# GBTx_MGT.net
KiCad netlist of a schematic drawn in Altium Designer
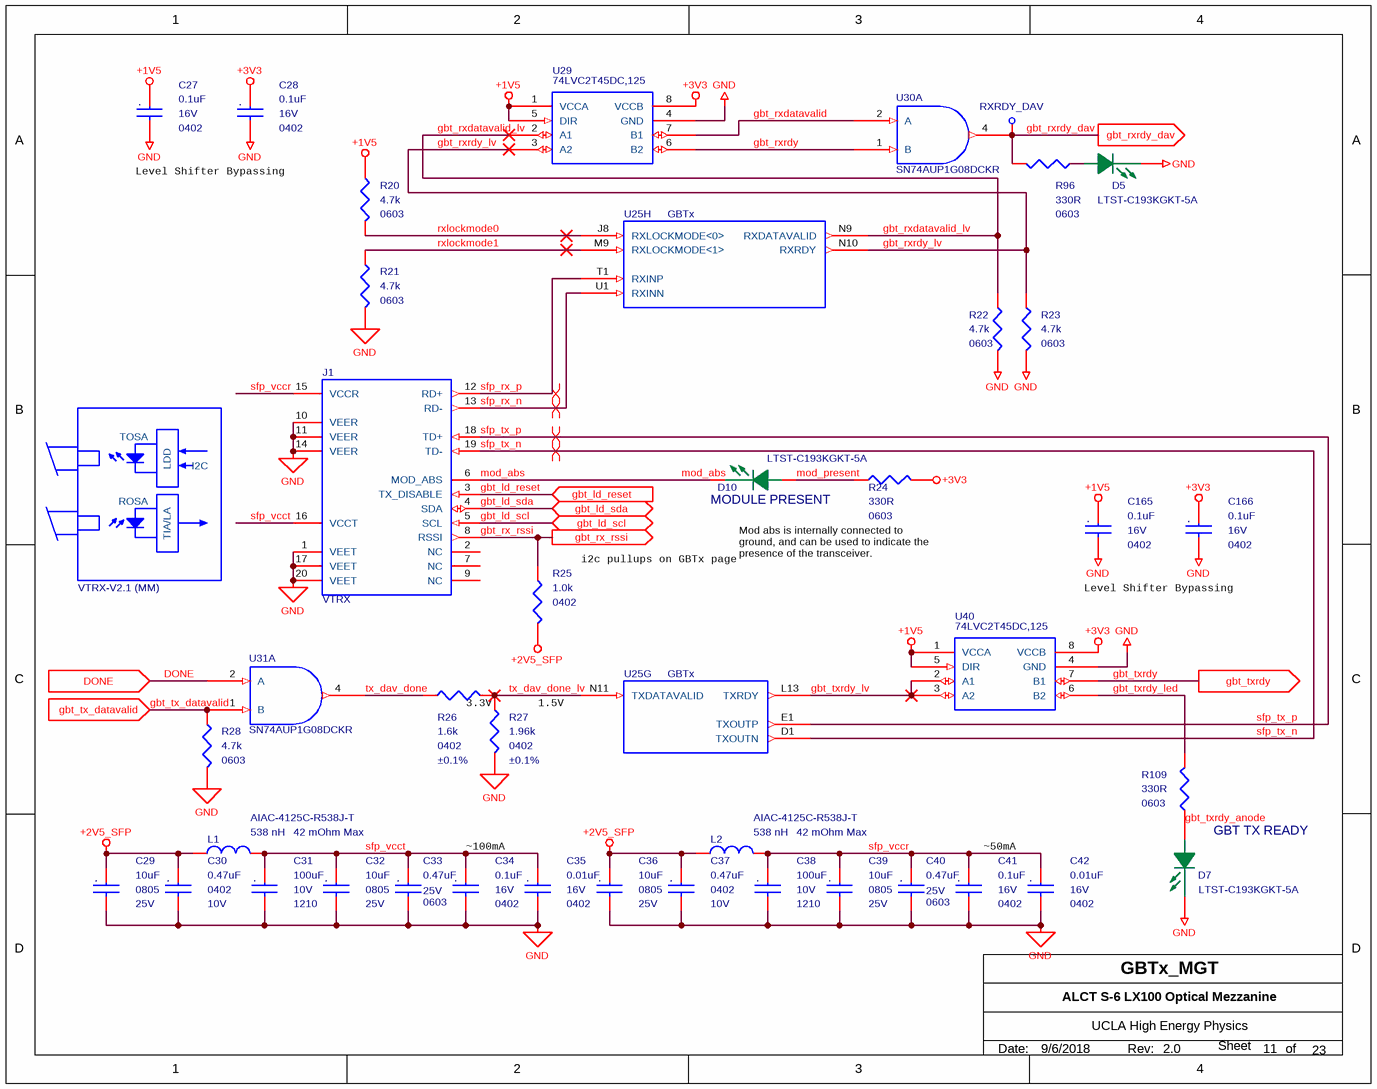
[diagram p0: GBTx_MGT.SchDoc]

(export (version "E")
  (design (tool "Eeschema 10.0.6"))
  (components
    (comp (ref "C27")
      (value "0.1uF")
      (footprint "MC_S6/SM/C_0402_IPC")
      (description "CAP CER 0.1UF 16V X7R 0402")
      (fields
        (field (name "MANUFACTURER") "KEMET")
        (field (name "MANUFACTURER PART NUMBER") "C0402C104K4RACTU")
        (field (name "PACKAGE") "0402")
        (field (name "VOLTAGE - RATED") "16V")
      )
      (libsource (lib "ALCT_MEZ_SPARTAN6_Library") (part "C0402C104K4RACTU"))
    )
    (comp (ref "C28")
      (value "0.1uF")
      (footprint "MC_S6/SM/C_0402_IPC")
      (description "CAP CER 0.1UF 16V X7R 0402")
      (fields
        (field (name "MANUFACTURER") "KEMET")
        (field (name "MANUFACTURER PART NUMBER") "C0402C104K4RACTU")
        (field (name "PACKAGE") "0402")
        (field (name "VOLTAGE - RATED") "16V")
      )
      (libsource (lib "ALCT_MEZ_SPARTAN6_Library") (part "C0402C104K4RACTU"))
    )
    (comp (ref "C29")
      (value "10uF")
      (footprint "MC_S6/SM/C_0805_IPC")
      (description "CAP CER 10UF 25V X5R 0805")
      (fields
        (field (name "MANUFACTURER") "Murata Electronics North America")
        (field (name "MANUFACTURER PART NUMBER") "GRM21BR61E106KA73L")
        (field (name "VOLTAGE - RATED") "25V")
        (field (name "PACKAGE") "0805")
      )
      (libsource (lib "ALCT_MEZ_SPARTAN6_Library") (part "GRM21BR61E106KA73L"))
    )
    (comp (ref "C30")
      (value "0.47uF")
      (footprint "MC_S6/SM/C_0402_IPC")
      (description "CAP CER 0.47UF 10V X5R 0402")
      (fields
        (field (name "MANUFACTURER") "Murata Electronics North America")
        (field (name "MANUFACTURER PART NUMBER") "GRM155R61A474KE15D")
        (field (name "VOLTAGE - RATED") "10V")
        (field (name "PACKAGE") "0402")
      )
      (libsource (lib "ALCT_MEZ_SPARTAN6_Library") (part "GRM155R61A474KE15D"))
    )
    (comp (ref "C31")
      (value "100uF")
      (footprint "MC_S6/SM/C_1210_IPC")
      (description "CAP CER 100UF 10V X5R 1210")
      (fields
        (field (name "MANUFACTURER") "Taiyo Yuden")
        (field (name "MANUFACTURER PART NUMBER") "LMK325BJ107MM-T")
        (field (name "VOLTAGE - RATED") "10V")
        (field (name "PACKAGE") "1210")
      )
      (libsource (lib "ALCT_MEZ_SPARTAN6_Library") (part "LMK325BJ107MM-T"))
    )
    (comp (ref "C32")
      (value "10uF")
      (footprint "MC_S6/SM/C_0805_IPC")
      (description "CAP CER 10UF 25V X5R 0805")
      (fields
        (field (name "MANUFACTURER") "Murata Electronics North America")
        (field (name "MANUFACTURER PART NUMBER") "GRM21BR61E106KA73L")
        (field (name "VOLTAGE - RATED") "25V")
        (field (name "PACKAGE") "0805")
      )
      (libsource (lib "ALCT_MEZ_SPARTAN6_Library") (part "GRM21BR61E106KA73L"))
    )
    (comp (ref "C33")
      (value "0.47uF")
      (footprint "MC_S6/SM/C_0603_IPC")
      (description "CAP CER 0.47UF 25V X7R 0603")
      (fields
        (field (name "MANUFACTURER") "Murata")
        (field (name "MANUFACTURER PART NUMBER") "GRM188R71E474KA12D")
        (field (name "VOLTAGE - RATED") "25V")
        (field (name "PACKAGE") "0603")
      )
      (libsource (lib "ALCT_MEZ_SPARTAN6_Library") (part "GRM188R71E474KA12D"))
    )
    (comp (ref "C34")
      (value "0.1uF")
      (footprint "MC_S6/SM/C_0402_IPC")
      (description "CAP CER 0.1UF 16V X7R 0402")
      (fields
        (field (name "MANUFACTURER") "KEMET")
        (field (name "MANUFACTURER PART NUMBER") "C0402C104K4RACTU")
        (field (name "PACKAGE") "0402")
        (field (name "VOLTAGE - RATED") "16V")
      )
      (libsource (lib "ALCT_MEZ_SPARTAN6_Library") (part "C0402C104K4RACTU"))
    )
    (comp (ref "C35")
      (value "0.01uF")
      (footprint "MC_S6/SM/C_0402_IPC")
      (description "CAP CER 10nF 16V X7R 0402")
      (fields
        (field (name "MANUFACTURER") "KEMET")
        (field (name "MANUFACTURER PART NUMBER") "C0402C103K4RACTU")
        (field (name "VOLTAGE - RATED") "16V")
        (field (name "PACKAGE") "0402")
      )
      (libsource (lib "ALCT_MEZ_SPARTAN6_Library") (part "C0402C103K4RACTU"))
    )
    (comp (ref "C36")
      (value "10uF")
      (footprint "MC_S6/SM/C_0805_IPC")
      (description "CAP CER 10UF 25V X5R 0805")
      (fields
        (field (name "MANUFACTURER") "Murata Electronics North America")
        (field (name "MANUFACTURER PART NUMBER") "GRM21BR61E106KA73L")
        (field (name "VOLTAGE - RATED") "25V")
        (field (name "PACKAGE") "0805")
      )
      (libsource (lib "ALCT_MEZ_SPARTAN6_Library") (part "GRM21BR61E106KA73L"))
    )
    (comp (ref "C37")
      (value "0.47uF")
      (footprint "MC_S6/SM/C_0402_IPC")
      (description "CAP CER 0.47UF 10V X5R 0402")
      (fields
        (field (name "MANUFACTURER") "Murata Electronics North America")
        (field (name "MANUFACTURER PART NUMBER") "GRM155R61A474KE15D")
        (field (name "VOLTAGE - RATED") "10V")
        (field (name "PACKAGE") "0402")
      )
      (libsource (lib "ALCT_MEZ_SPARTAN6_Library") (part "GRM155R61A474KE15D"))
    )
    (comp (ref "C38")
      (value "100uF")
      (footprint "MC_S6/SM/C_1210_IPC")
      (description "CAP CER 100UF 10V X5R 1210")
      (fields
        (field (name "MANUFACTURER") "Taiyo Yuden")
        (field (name "MANUFACTURER PART NUMBER") "LMK325BJ107MM-T")
        (field (name "VOLTAGE - RATED") "10V")
        (field (name "PACKAGE") "1210")
      )
      (libsource (lib "ALCT_MEZ_SPARTAN6_Library") (part "LMK325BJ107MM-T"))
    )
    (comp (ref "C39")
      (value "10uF")
      (footprint "MC_S6/SM/C_0805_IPC")
      (description "CAP CER 10UF 25V X5R 0805")
      (fields
        (field (name "MANUFACTURER") "Murata Electronics North America")
        (field (name "MANUFACTURER PART NUMBER") "GRM21BR61E106KA73L")
        (field (name "VOLTAGE - RATED") "25V")
        (field (name "PACKAGE") "0805")
      )
      (libsource (lib "ALCT_MEZ_SPARTAN6_Library") (part "GRM21BR61E106KA73L"))
    )
    (comp (ref "C40")
      (value "0.47uF")
      (footprint "MC_S6/SM/C_0603_IPC")
      (description "CAP CER 0.47UF 25V X7R 0603")
      (fields
        (field (name "MANUFACTURER") "Murata")
        (field (name "MANUFACTURER PART NUMBER") "GRM188R71E474KA12D")
        (field (name "VOLTAGE - RATED") "25V")
        (field (name "PACKAGE") "0603")
      )
      (libsource (lib "ALCT_MEZ_SPARTAN6_Library") (part "GRM188R71E474KA12D"))
    )
    (comp (ref "C41")
      (value "0.1uF")
      (footprint "MC_S6/SM/C_0402_IPC")
      (description "CAP CER 0.1UF 16V X7R 0402")
      (fields
        (field (name "MANUFACTURER") "KEMET")
        (field (name "MANUFACTURER PART NUMBER") "C0402C104K4RACTU")
        (field (name "PACKAGE") "0402")
        (field (name "VOLTAGE - RATED") "16V")
      )
      (libsource (lib "ALCT_MEZ_SPARTAN6_Library") (part "C0402C104K4RACTU"))
    )
    (comp (ref "C42")
      (value "0.01uF")
      (footprint "MC_S6/SM/C_0402_IPC")
      (description "CAP CER 10nF 16V X7R 0402")
      (fields
        (field (name "MANUFACTURER") "KEMET")
        (field (name "MANUFACTURER PART NUMBER") "C0402C103K4RACTU")
        (field (name "VOLTAGE - RATED") "16V")
        (field (name "PACKAGE") "0402")
      )
      (libsource (lib "ALCT_MEZ_SPARTAN6_Library") (part "C0402C103K4RACTU"))
    )
    (comp (ref "C165")
      (value "0.1uF")
      (footprint "MC_S6/SM/C_0402_IPC")
      (description "CAP CER 0.1UF 16V X7R 0402")
      (fields
        (field (name "MANUFACTURER") "KEMET")
        (field (name "MANUFACTURER PART NUMBER") "C0402C104K4RACTU")
        (field (name "PACKAGE") "0402")
        (field (name "VOLTAGE - RATED") "16V")
      )
      (libsource (lib "ALCT_MEZ_SPARTAN6_Library") (part "C0402C104K4RACTU"))
    )
    (comp (ref "C166")
      (value "0.1uF")
      (footprint "MC_S6/SM/C_0402_IPC")
      (description "CAP CER 0.1UF 16V X7R 0402")
      (fields
        (field (name "MANUFACTURER") "KEMET")
        (field (name "MANUFACTURER PART NUMBER") "C0402C104K4RACTU")
        (field (name "PACKAGE") "0402")
        (field (name "VOLTAGE - RATED") "16V")
      )
      (libsource (lib "ALCT_MEZ_SPARTAN6_Library") (part "C0402C104K4RACTU"))
    )
    (comp (ref "D5")
      (value "LTST-C193KGKT-5A")
      (footprint "MC_S6/SM/LED_0603")
      (description "LED GREEN CLEAR 0603 SMD")
      (fields (field (name "MANUFACTURER") "Lite-On Inc."))
      (libsource (lib "ALCT_MEZ_SPARTAN6_Library") (part "LTST-C193KGKT-5A"))
    )
    (comp (ref "D7")
      (value "LTST-C193KGKT-5A")
      (footprint "MC_S6/SM/LED_0603")
      (description "LED GREEN CLEAR 0603 SMD")
      (fields (field (name "MANUFACTURER") "Lite-On Inc."))
      (libsource (lib "ALCT_MEZ_SPARTAN6_Library") (part "LTST-C193KGKT-5A"))
    )
    (comp (ref "D10")
      (value "LTST-C193KGKT-5A")
      (footprint "MC_S6/SM/LED_0603")
      (description "LED GREEN CLEAR 0603 SMD")
      (fields (field (name "MANUFACTURER") "Lite-On Inc."))
      (libsource (lib "ALCT_MEZ_SPARTAN6_Library") (part "LTST-C193KGKT-5A"))
    )
    (comp (ref "J1")
      (value "VTRX")
      (footprint "MC_S6/SM/TE-1888247-1")
      (description "CONN FP+ CAGE 30AU SMD")
      (fields
        (field (name "MANUFACTURER") "TE Connectivity AMP Connectors")
        (field (name "MANUFACTURER PART NUMBER") "1888247-1")
      )
      (libsource (lib "ALCT_MEZ_SPARTAN6_Library") (part "VTRX"))
    )
    (comp (ref "L1")
      (value "538 nH")
      (footprint "AIAC-4125C-R538J")
      (description "IND 538NH 2A 42 MOHM SMD")
      (fields
        (field (name "MANUFACTURER") "Abracon LLC")
        (field (name "TOLERANCE") "±5%")
        (field (name "MANUFACTURER PART NUMBER") "AIAC-4125C-R538J-T")
        (field (name "DC RESISTANCE (DCR)") "42 mOhm Max")
      )
      (libsource (lib "ALCT_MEZ_SPARTAN6_Library") (part "AIAC-4125C-R538J"))
    )
    (comp (ref "L2")
      (value "538 nH")
      (footprint "AIAC-4125C-R538J")
      (description "IND 538NH 2A 42 MOHM SMD")
      (fields
        (field (name "MANUFACTURER") "Abracon LLC")
        (field (name "TOLERANCE") "±5%")
        (field (name "MANUFACTURER PART NUMBER") "AIAC-4125C-R538J-T")
        (field (name "DC RESISTANCE (DCR)") "42 mOhm Max")
      )
      (libsource (lib "ALCT_MEZ_SPARTAN6_Library") (part "AIAC-4125C-R538J"))
    )
    (comp (ref "PCBM1")
      (value "VTRX-V2.1 (MM)")
      (footprint "PCBM_CERN_VTRX V2.1 (MM)")
      (description "CERN VTRX V2.1 Multi-Mode (MM)")
      (fields
        (field (name "PART NUMBER") "PCBM_CERN_VTRX V2.1 (MM)_a")
        (field (name "MANUFACTURER") "CERN")
        (field (name "MANUFACTURER PART NUMBER") "VTRX-V2.1 (MM)")
        (field (name "AUTHOR") "CERN DEM JLC")
      )
      (libsource (lib "VTRX-VTTX") (part "PCBM_CERN_VTRX V2.1 (MM)_a"))
    )
    (comp (ref "R20")
      (value "4.7k")
      (footprint "MC_S6/SM/R_0603_IPC")
      (description "RES SMD 4.7K OHM 1% 1/10W 0603")
      (fields
        (field (name "TOLERANCE") "±1%")
        (field (name "MANUFACTURER") "Bourns Inc.")
        (field (name "SUPPLIER DEVICE PACKAGE") "0603")
      )
      (libsource (lib "ALCT_MEZ_SPARTAN6_Library") (part "CR0603-FX-4701ELF"))
    )
    (comp (ref "R21")
      (value "4.7k")
      (footprint "MC_S6/SM/R_0603_IPC")
      (description "RES SMD 4.7K OHM 1% 1/10W 0603")
      (fields
        (field (name "MANUFACTURER") "Bourns Inc.")
        (field (name "MANUFACTURER PART NUMBER") "CR0603-FX-4701ELF")
        (field (name "SUPPLIER DEVICE PACKAGE") "0603")
      )
      (libsource (lib "ALCT_MEZ_SPARTAN6_Library") (part "CR0603-FX-4701ELF"))
    )
    (comp (ref "R22")
      (value "4.7k")
      (footprint "MC_S6/SM/R_0603_IPC")
      (description "RES SMD 4.7K OHM 1% 1/10W 0603")
      (fields
        (field (name "MANUFACTURER") "Bourns Inc.")
        (field (name "MANUFACTURER PART NUMBER") "CR0603-FX-4701ELF")
        (field (name "SUPPLIER DEVICE PACKAGE") "0603")
      )
      (libsource (lib "ALCT_MEZ_SPARTAN6_Library") (part "CR0603-FX-4701ELF"))
    )
    (comp (ref "R23")
      (value "4.7k")
      (footprint "MC_S6/SM/R_0603_IPC")
      (description "RES SMD 4.7K OHM 1% 1/10W 0603")
      (fields
        (field (name "MANUFACTURER") "Bourns Inc.")
        (field (name "MANUFACTURER PART NUMBER") "CR0603-FX-4701ELF")
        (field (name "SUPPLIER DEVICE PACKAGE") "0603")
      )
      (libsource (lib "ALCT_MEZ_SPARTAN6_Library") (part "CR0603-FX-4701ELF"))
    )
    (comp (ref "R24")
      (value "330R")
      (footprint "MC_S6/SM/R_0603_IPC")
      (description "RES SMD 330 OHM 1% 1/10W 0603")
      (fields
        (field (name "TOLERANCE") "±1%")
        (field (name "MANUFACTURER") "Bourns Inc.")
        (field (name "SUPPLIER DEVICE PACKAGE") "0603")
      )
      (libsource (lib "ALCT_MEZ_SPARTAN6_Library") (part "CR0603-FX-3300ELF"))
    )
    (comp (ref "R25")
      (value "1.0k")
      (footprint "MC_S6/SM/R_0402_IPC")
      (description "RES SMD 1.0K OHM 0.1% 1/16W 0402")
      (fields
        (field (name "TOLERANCE") "±0.1%")
        (field (name "MANUFACTURER") "Panasonic Electronic Components")
        (field (name "PACKAGE") "0402")
      )
      (libsource (lib "ALCT_MEZ_SPARTAN6_Library") (part "ERA-2AEB102X"))
    )
    (comp (ref "R26")
      (value "1.6k")
      (footprint "MC_S6/SM/R_0402_IPC")
      (description "RES SMD 1.6K OHM 0.1% 1/16W 0402")
      (fields
        (field (name "MANUFACTURER") "Panasonic Electronic Components")
        (field (name "MANUFACTURER PART NUMBER") "ERA-2AEB162X")
        (field (name "TOLERANCE") "±0.1%")
        (field (name "PACKAGE") "0402")
      )
      (libsource (lib "ALCT_MEZ_SPARTAN6_Library") (part "ERA-2AEB162X"))
    )
    (comp (ref "R27")
      (value "1.96k")
      (footprint "MC_S6/SM/R_0402_IPC")
      (description "RES SMD 1.96K OHM 0.1% 1/16W 0402")
      (fields
        (field (name "MANUFACTURER") "Panasonic Electronic Components")
        (field (name "MANUFACTURER PART NUMBER") "ERA-2AEB1961X")
        (field (name "TOLERANCE") "±0.1%")
        (field (name "PACKAGE") "0402")
      )
      (libsource (lib "ALCT_MEZ_SPARTAN6_Library") (part "ERA-2AEB1961X"))
    )
    (comp (ref "R28")
      (value "4.7k")
      (footprint "MC_S6/SM/R_0603_IPC")
      (description "RES SMD 4.7K OHM 1% 1/10W 0603")
      (fields
        (field (name "MANUFACTURER") "Bourns Inc.")
        (field (name "MANUFACTURER PART NUMBER") "CR0603-FX-4701ELF")
        (field (name "SUPPLIER DEVICE PACKAGE") "0603")
      )
      (libsource (lib "ALCT_MEZ_SPARTAN6_Library") (part "CR0603-FX-4701ELF"))
    )
    (comp (ref "R96")
      (value "330R")
      (footprint "MC_S6/SM/R_0603_IPC")
      (description "RES SMD 330 OHM 1% 1/10W 0603")
      (fields
        (field (name "TOLERANCE") "±1%")
        (field (name "MANUFACTURER") "Bourns Inc.")
        (field (name "SUPPLIER DEVICE PACKAGE") "0603")
      )
      (libsource (lib "ALCT_MEZ_SPARTAN6_Library") (part "CR0603-FX-3300ELF"))
    )
    (comp (ref "R109")
      (value "330R")
      (footprint "MC_S6/SM/R_0603_IPC")
      (description "RES SMD 330 OHM 1% 1/10W 0603")
      (fields
        (field (name "TOLERANCE") "±1%")
        (field (name "MANUFACTURER") "Bourns Inc.")
        (field (name "SUPPLIER DEVICE PACKAGE") "0603")
      )
      (libsource (lib "ALCT_MEZ_SPARTAN6_Library") (part "CR0603-FX-3300ELF"))
    )
    (comp (ref "RXRDY_DAV")
      (value "Test Point Via")
      (footprint "MC_S6/TH/TPVIA")
      (libsource (lib "ALCT_MEZ_SPARTAN6_Library") (part "TPVIA"))
    )
    (comp (ref "U25")
      (value "GBTx")
      (footprint "BGA400 GBT")
      (libsource (lib "ALCT_MEZ_SPARTAN6_Library") (part "GBTx"))
    )
    (comp (ref "U29")
      (value "74LVC2T45DC,125")
      (footprint "VSSOP8 SOT765-1")
      (description "IC TRNSLTR BIDIRECTIONAL 8VSSOP")
      (fields (field (name "MANUFACTURER") "Nexperia USA Inc.") (field (name "BASE PART NUMBER") "74LVC2T45"))
      (libsource (lib "ALCT_MEZ_SPARTAN6_Library") (part "74LVC2T45DC,125"))
    )
    (comp (ref "U30")
      (value "SN74AUP1G08DCKR")
      (footprint "MC_S6/SM/SOT_SC70_DCK5")
      (description "IC GATE AND 1CH 2-INP 5-TSSOP")
      (fields
        (field (name "MANUFACTURER") "Texas Instruments")
        (field (name "MANUFACTURER PART NUMBER") "SN74AUP1G08DCKT")
      )
      (libsource (lib "ALCT_MEZ_SPARTAN6_Library") (part "SN74AUP1G08DCKR"))
    )
    (comp (ref "U31")
      (value "SN74AUP1G08DCKR")
      (footprint "MC_S6/SM/SOT_SC70_DCK5")
      (description "IC GATE AND 1CH 2-INP 5-TSSOP")
      (fields
        (field (name "MANUFACTURER") "Texas Instruments")
        (field (name "MANUFACTURER PART NUMBER") "SN74AUP1G08DCKT")
      )
      (libsource (lib "ALCT_MEZ_SPARTAN6_Library") (part "SN74AUP1G08DCKR"))
    )
    (comp (ref "U40")
      (value "74LVC2T45DC,125")
      (footprint "VSSOP8 SOT765-1")
      (description "IC TRNSLTR BIDIRECTIONAL 8VSSOP")
      (fields (field (name "MANUFACTURER") "Nexperia USA Inc.") (field (name "BASE PART NUMBER") "74LVC2T45"))
      (libsource (lib "ALCT_MEZ_SPARTAN6_Library") (part "74LVC2T45DC,125"))
    )
  )
  (nets
    (net (code "1") (name "+1V5") (class "Default")
      (node (ref "C165") (pin "1") (pinfunction "1_1") (pintype "passive"))
      (node (ref "C27") (pin "1") (pinfunction "1_1") (pintype "passive"))
      (node (ref "R20") (pin "1") (pinfunction "1_1") (pintype "passive"))
      (node (ref "U29") (pin "1") (pinfunction "VCCA_1") (pintype "power_in"))
      (node (ref "U29") (pin "5") (pinfunction "DIR_5") (pintype "input"))
      (node (ref "U40") (pin "1") (pinfunction "VCCA_1") (pintype "power_in"))
      (node (ref "U40") (pin "5") (pinfunction "DIR_5") (pintype "input"))
    )
    (net (code "2") (name "+2V5_SFP") (class "Default")
      (node (ref "C29") (pin "1") (pinfunction "1_1") (pintype "passive"))
      (node (ref "C30") (pin "1") (pinfunction "1_1") (pintype "passive"))
      (node (ref "C36") (pin "1") (pinfunction "1_1") (pintype "passive"))
      (node (ref "C37") (pin "1") (pinfunction "1_1") (pintype "passive"))
      (node (ref "L1") (pin "2") (pinfunction "2_2") (pintype "passive"))
      (node (ref "L2") (pin "2") (pinfunction "2_2") (pintype "passive"))
      (node (ref "R25") (pin "2") (pinfunction "2_2") (pintype "passive"))
    )
    (net (code "3") (name "+3V3") (class "Default")
      (node (ref "C166") (pin "1") (pinfunction "1_1") (pintype "passive"))
      (node (ref "C28") (pin "1") (pinfunction "1_1") (pintype "passive"))
      (node (ref "R24") (pin "2") (pinfunction "2_2") (pintype "passive"))
      (node (ref "U29") (pin "8") (pinfunction "VCCB_8") (pintype "passive"))
      (node (ref "U40") (pin "8") (pinfunction "VCCB_8") (pintype "passive"))
    )
    (net (code "4") (name "/DONE") (class "Default")
      (node (ref "U31") (pin "2") (pinfunction "A_2") (pintype "input"))
    )
    (net (code "5") (name "/gbt_ld_reset") (class "Default")
      (node (ref "J1") (pin "3") (pinfunction "TX_DISABLE_3") (pintype "input"))
    )
    (net (code "6") (name "/gbt_ld_scl") (class "Default")
      (node (ref "J1") (pin "5") (pinfunction "SCL_5") (pintype "input"))
    )
    (net (code "7") (name "/gbt_ld_sda") (class "Default")
      (node (ref "J1") (pin "4") (pinfunction "SDA_4") (pintype "bidirectional"))
    )
    (net (code "8") (name "/gbt_rx_rssi") (class "Default")
      (node (ref "J1") (pin "8") (pinfunction "RSSI_8") (pintype "output"))
      (node (ref "R25") (pin "1") (pinfunction "1_1") (pintype "passive"))
    )
    (net (code "9") (name "/gbt_rxdatavalid") (class "Default")
      (node (ref "U29") (pin "7") (pinfunction "B1_7") (pintype "bidirectional"))
      (node (ref "U30") (pin "2") (pinfunction "A_2") (pintype "input"))
    )
    (net (code "10") (name "/gbt_rxdatavalid_lv") (class "Default")
      (node (ref "R22") (pin "1") (pinfunction "1_1") (pintype "passive"))
      (node (ref "U25") (pin "N9") (pinfunction "RXDATAVALID_N9") (pintype "output"))
      (node (ref "U29") (pin "2") (pinfunction "A1_2") (pintype "bidirectional"))
    )
    (net (code "11") (name "/gbt_rxrdy") (class "Default")
      (node (ref "U29") (pin "6") (pinfunction "B2_6") (pintype "bidirectional"))
      (node (ref "U30") (pin "1") (pinfunction "B_1") (pintype "input"))
    )
    (net (code "12") (name "/gbt_rxrdy_dav") (class "Default")
      (node (ref "R96") (pin "2") (pinfunction "2_2") (pintype "passive"))
      (node (ref "RXRDY_DAV") (pin "1") (pinfunction "In_1") (pintype "passive"))
      (node (ref "U30") (pin "4") (pinfunction "Y_4") (pintype "output"))
    )
    (net (code "13") (name "/gbt_rxrdy_lv") (class "Default")
      (node (ref "R23") (pin "1") (pinfunction "1_1") (pintype "passive"))
      (node (ref "U25") (pin "N10") (pinfunction "RXRDY_N10") (pintype "output"))
      (node (ref "U29") (pin "3") (pinfunction "A2_3") (pintype "bidirectional"))
    )
    (net (code "14") (name "/gbt_tx_datavalid") (class "Default")
      (node (ref "R28") (pin "1") (pinfunction "1_1") (pintype "passive"))
      (node (ref "U31") (pin "1") (pinfunction "B_1") (pintype "input"))
    )
    (net (code "15") (name "/gbt_txrdy") (class "Default")
      (node (ref "U40") (pin "7") (pinfunction "B1_7") (pintype "bidirectional"))
    )
    (net (code "16") (name "/gbt_txrdy_anode") (class "Default")
      (node (ref "D7") (pin "A") (pinfunction "ANODE_A") (pintype "passive"))
      (node (ref "R109") (pin "1") (pinfunction "1_1") (pintype "passive"))
    )
    (net (code "17") (name "/gbt_txrdy_led") (class "Default")
      (node (ref "R109") (pin "2") (pinfunction "2_2") (pintype "passive"))
      (node (ref "U40") (pin "6") (pinfunction "B2_6") (pintype "bidirectional"))
    )
    (net (code "18") (name "/gbt_txrdy_lv") (class "Default")
      (node (ref "U25") (pin "L13") (pinfunction "TXRDY_L13") (pintype "output"))
      (node (ref "U40") (pin "2") (pinfunction "A1_2") (pintype "bidirectional"))
      (node (ref "U40") (pin "3") (pinfunction "A2_3") (pintype "bidirectional"))
    )
    (net (code "19") (name "/mod_abs") (class "Default")
      (node (ref "D10") (pin "K") (pinfunction "CATHODE_K") (pintype "passive"))
      (node (ref "J1") (pin "6") (pinfunction "MOD_ABS_6") (pintype "passive"))
    )
    (net (code "20") (name "/mod_present") (class "Default")
      (node (ref "D10") (pin "A") (pinfunction "ANODE_A") (pintype "passive"))
      (node (ref "R24") (pin "1") (pinfunction "1_1") (pintype "passive"))
    )
    (net (code "21") (name "/rxlockmode0") (class "Default")
      (node (ref "R20") (pin "2") (pinfunction "2_2") (pintype "passive"))
      (node (ref "U25") (pin "J8") (pinfunction "RXLOCKMODE<0>_J8") (pintype "input"))
    )
    (net (code "22") (name "/rxlockmode1") (class "Default")
      (node (ref "R21") (pin "1") (pinfunction "1_1") (pintype "passive"))
      (node (ref "U25") (pin "M9") (pinfunction "RXLOCKMODE<1>_M9") (pintype "input"))
    )
    (net (code "23") (name "/sfp_rx_n") (class "Default")
      (node (ref "J1") (pin "13") (pinfunction "RD-_13") (pintype "output"))
      (node (ref "U25") (pin "U1") (pinfunction "RXINN_U1") (pintype "input"))
    )
    (net (code "24") (name "/sfp_rx_p") (class "Default")
      (node (ref "J1") (pin "12") (pinfunction "RD+_12") (pintype "output"))
      (node (ref "U25") (pin "T1") (pinfunction "RXINP_T1") (pintype "input"))
    )
    (net (code "25") (name "/sfp_tx_n") (class "Default")
      (node (ref "J1") (pin "19") (pinfunction "TD-_19") (pintype "input"))
      (node (ref "U25") (pin "D1") (pinfunction "TXOUTN_D1") (pintype "output"))
    )
    (net (code "26") (name "/sfp_tx_p") (class "Default")
      (node (ref "J1") (pin "18") (pinfunction "TD+_18") (pintype "input"))
      (node (ref "U25") (pin "E1") (pinfunction "TXOUTP_E1") (pintype "output"))
    )
    (net (code "27") (name "/sfp_vccr") (class "Default")
      (node (ref "C38") (pin "1") (pinfunction "1_1") (pintype "passive"))
      (node (ref "C39") (pin "1") (pinfunction "1_1") (pintype "passive"))
      (node (ref "C40") (pin "1") (pinfunction "1_1") (pintype "passive"))
      (node (ref "C41") (pin "1") (pinfunction "1_1") (pintype "passive"))
      (node (ref "C42") (pin "1") (pinfunction "1_1") (pintype "passive"))
      (node (ref "J1") (pin "15") (pinfunction "VCCR_15") (pintype "passive"))
      (node (ref "L2") (pin "1") (pinfunction "1_1") (pintype "passive"))
    )
    (net (code "28") (name "/sfp_vcct") (class "Default")
      (node (ref "C31") (pin "1") (pinfunction "1_1") (pintype "passive"))
      (node (ref "C32") (pin "1") (pinfunction "1_1") (pintype "passive"))
      (node (ref "C33") (pin "1") (pinfunction "1_1") (pintype "passive"))
      (node (ref "C34") (pin "1") (pinfunction "1_1") (pintype "passive"))
      (node (ref "C35") (pin "1") (pinfunction "1_1") (pintype "passive"))
      (node (ref "J1") (pin "16") (pinfunction "VCCT_16") (pintype "passive"))
      (node (ref "L1") (pin "1") (pinfunction "1_1") (pintype "passive"))
    )
    (net (code "29") (name "/tx_dav_done") (class "Default")
      (node (ref "R26") (pin "1") (pinfunction "1_1") (pintype "passive"))
      (node (ref "U31") (pin "4") (pinfunction "Y_4") (pintype "output"))
    )
    (net (code "30") (name "/tx_dav_done_lv") (class "Default")
      (node (ref "R26") (pin "2") (pinfunction "2_2") (pintype "passive"))
      (node (ref "R27") (pin "1") (pinfunction "1_1") (pintype "passive"))
      (node (ref "U25") (pin "N11") (pinfunction "TXDATAVALID_N11") (pintype "input"))
    )
    (net (code "31") (name "GND") (class "Default")
      (node (ref "C165") (pin "2") (pinfunction "2_2") (pintype "passive"))
      (node (ref "C166") (pin "2") (pinfunction "2_2") (pintype "passive"))
      (node (ref "C27") (pin "2") (pinfunction "2_2") (pintype "passive"))
      (node (ref "C28") (pin "2") (pinfunction "2_2") (pintype "passive"))
      (node (ref "C29") (pin "2") (pinfunction "2_2") (pintype "passive"))
      (node (ref "C30") (pin "2") (pinfunction "2_2") (pintype "passive"))
      (node (ref "C31") (pin "2") (pinfunction "2_2") (pintype "passive"))
      (node (ref "C32") (pin "2") (pinfunction "2_2") (pintype "passive"))
      (node (ref "C33") (pin "2") (pinfunction "2_2") (pintype "passive"))
      (node (ref "C34") (pin "2") (pinfunction "2_2") (pintype "passive"))
      (node (ref "C35") (pin "2") (pinfunction "2_2") (pintype "passive"))
      (node (ref "C36") (pin "2") (pinfunction "2_2") (pintype "passive"))
      (node (ref "C37") (pin "2") (pinfunction "2_2") (pintype "passive"))
      (node (ref "C38") (pin "2") (pinfunction "2_2") (pintype "passive"))
      (node (ref "C39") (pin "2") (pinfunction "2_2") (pintype "passive"))
      (node (ref "C40") (pin "2") (pinfunction "2_2") (pintype "passive"))
      (node (ref "C41") (pin "2") (pinfunction "2_2") (pintype "passive"))
      (node (ref "C42") (pin "2") (pinfunction "2_2") (pintype "passive"))
      (node (ref "D5") (pin "K") (pinfunction "CATHODE_K") (pintype "passive"))
      (node (ref "D7") (pin "K") (pinfunction "CATHODE_K") (pintype "passive"))
      (node (ref "J1") (pin "1") (pinfunction "VEET_1") (pintype "passive"))
      (node (ref "J1") (pin "10") (pinfunction "VEER_10") (pintype "passive"))
      (node (ref "J1") (pin "11") (pinfunction "VEER_11") (pintype "passive"))
      (node (ref "J1") (pin "14") (pinfunction "VEER_14") (pintype "passive"))
      (node (ref "J1") (pin "17") (pinfunction "VEET_17") (pintype "passive"))
      (node (ref "J1") (pin "20") (pinfunction "VEET_20") (pintype "passive"))
      (node (ref "R21") (pin "2") (pinfunction "2_2") (pintype "passive"))
      (node (ref "R22") (pin "2") (pinfunction "2_2") (pintype "passive"))
      (node (ref "R23") (pin "2") (pinfunction "2_2") (pintype "passive"))
      (node (ref "R27") (pin "2") (pinfunction "2_2") (pintype "passive"))
      (node (ref "R28") (pin "2") (pinfunction "2_2") (pintype "passive"))
      (node (ref "U29") (pin "4") (pinfunction "GND_4") (pintype "power_in"))
      (node (ref "U40") (pin "4") (pinfunction "GND_4") (pintype "power_in"))
    )
    (net (code "32") (name "Net-(D5-ANODE)") (class "Default")
      (node (ref "D5") (pin "A") (pinfunction "ANODE_A") (pintype "passive"))
      (node (ref "R96") (pin "1") (pinfunction "1_1") (pintype "passive"))
    )
    (net (code "33") (name "unconnected-(J1-NC-Pad2)") (class "Default")
      (node (ref "J1") (pin "2") (pinfunction "NC_2") (pintype "passive"))
    )
    (net (code "34") (name "unconnected-(J1-NC-Pad7)") (class "Default")
      (node (ref "J1") (pin "7") (pinfunction "NC_7") (pintype "passive"))
    )
    (net (code "35") (name "unconnected-(J1-NC-Pad9)") (class "Default")
      (node (ref "J1") (pin "9") (pinfunction "NC_9") (pintype "passive"))
    )
  )
)
